# CarTalk.net
KiCad netlist of a schematic drawn in EAGLE
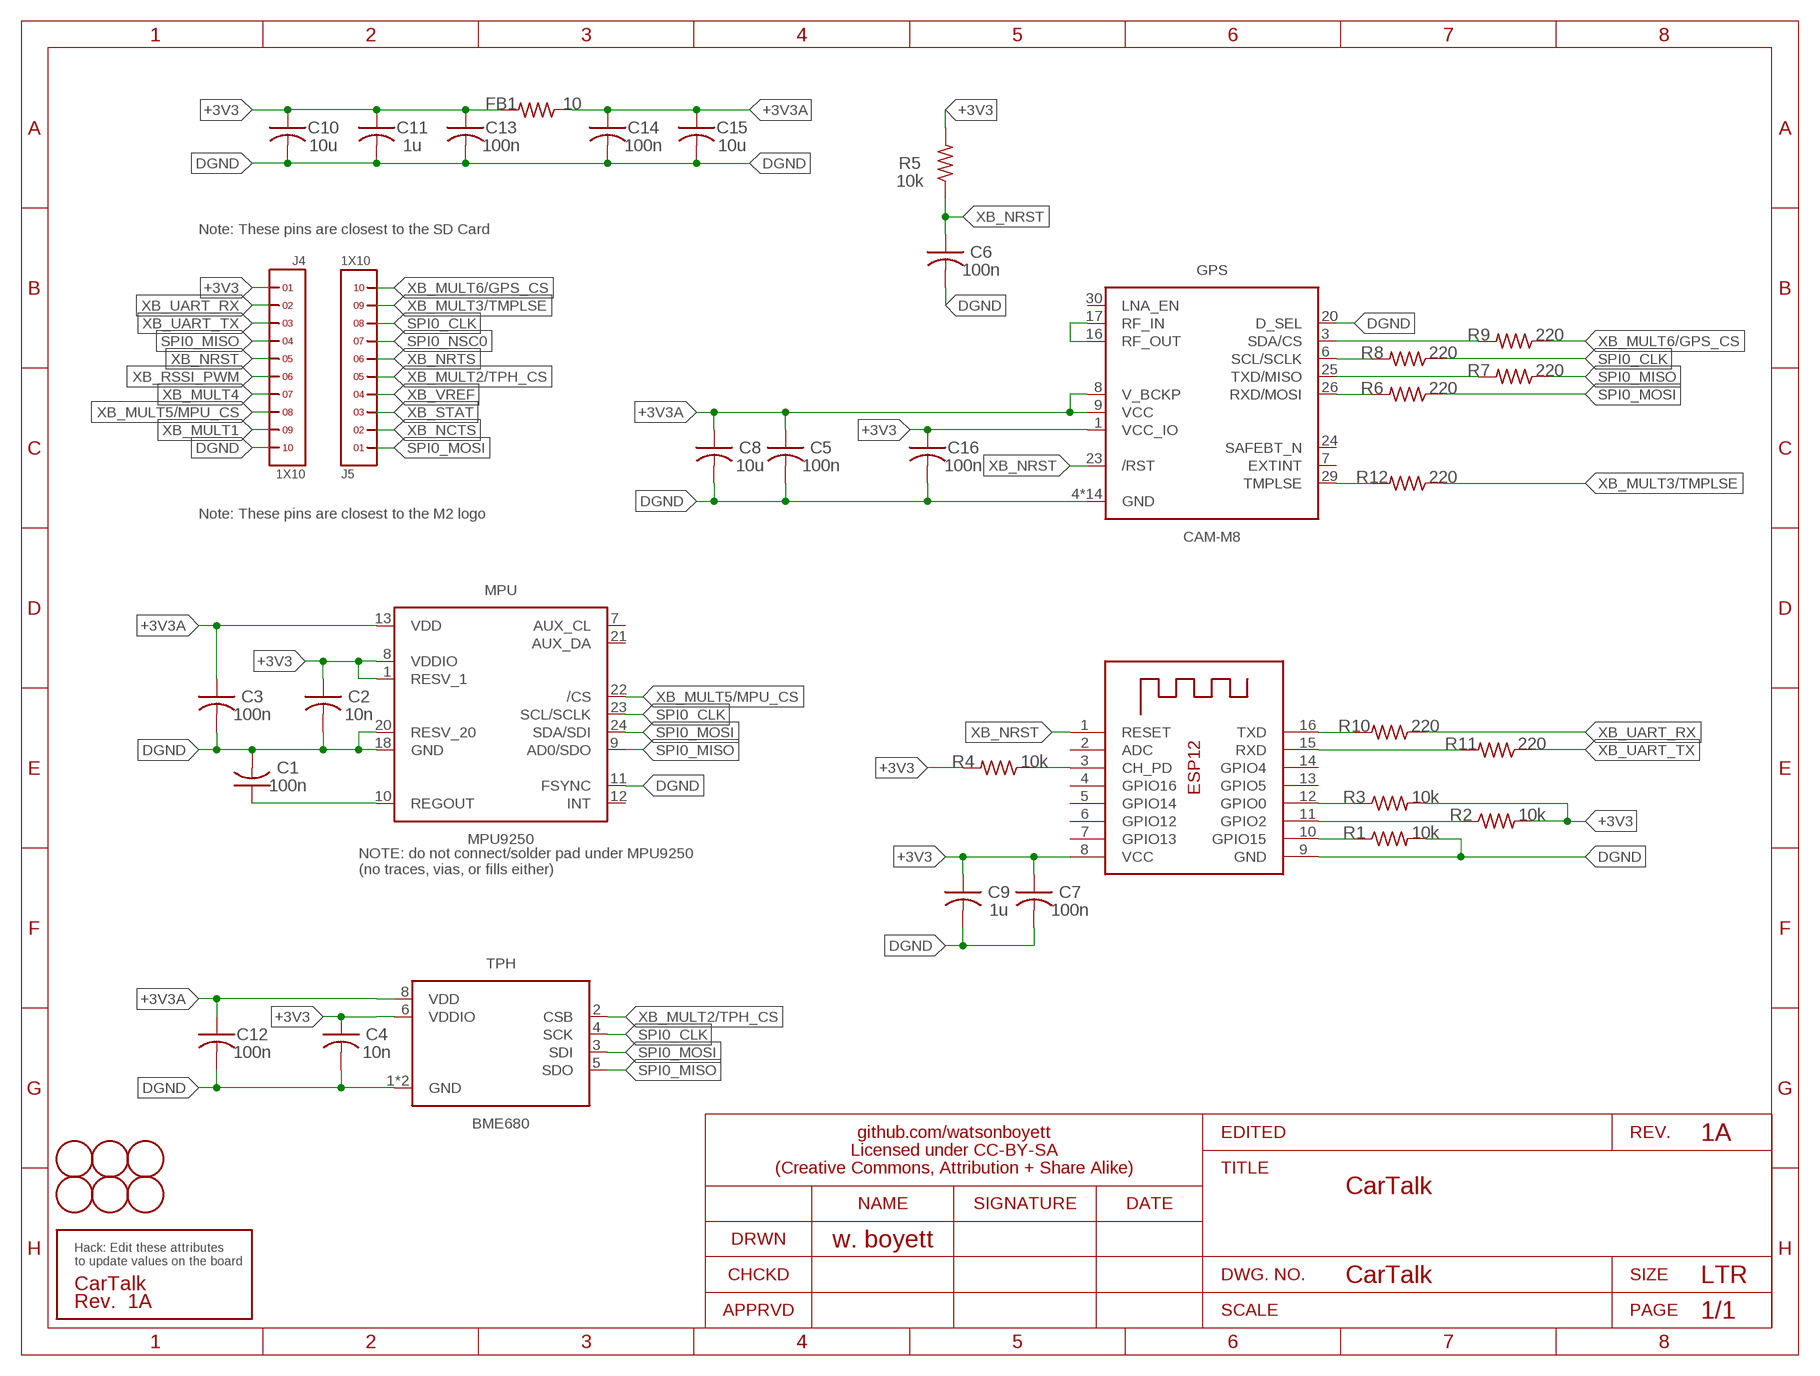
[diagram p0: schematic, sheet 1]

(export (version "E")
  (design (tool "Eeschema 10.0.6"))
  (components
    (comp (ref "C1")
      (value "100n")
      (footprint "eagle-import:C0603")
      (libsource (lib "eagle-import") (part "C-USC0603"))
    )
    (comp (ref "C2")
      (value "10n")
      (footprint "eagle-import:C0603")
      (libsource (lib "eagle-import") (part "C-USC0603"))
    )
    (comp (ref "C3")
      (value "100n")
      (footprint "eagle-import:C0603")
      (libsource (lib "eagle-import") (part "C-USC0603"))
    )
    (comp (ref "C4")
      (value "10n")
      (footprint "eagle-import:C0603")
      (libsource (lib "eagle-import") (part "C-USC0603"))
    )
    (comp (ref "C5")
      (value "100n")
      (footprint "eagle-import:C0603")
      (libsource (lib "eagle-import") (part "C-USC0603"))
    )
    (comp (ref "C6")
      (value "100n")
      (footprint "eagle-import:C0603")
      (libsource (lib "eagle-import") (part "C-USC0603"))
    )
    (comp (ref "C7")
      (value "100n")
      (footprint "eagle-import:C0603")
      (libsource (lib "eagle-import") (part "C-USC0603"))
    )
    (comp (ref "C8")
      (value "10u")
      (footprint "eagle-import:C0805")
      (libsource (lib "eagle-import") (part "C-USC0805"))
    )
    (comp (ref "C9")
      (value "1u")
      (footprint "eagle-import:C0603")
      (libsource (lib "eagle-import") (part "C-USC0603"))
    )
    (comp (ref "C10")
      (value "10u")
      (footprint "eagle-import:C0805")
      (libsource (lib "eagle-import") (part "C-USC0805"))
    )
    (comp (ref "C11")
      (value "1u")
      (footprint "eagle-import:C0603")
      (libsource (lib "eagle-import") (part "C-USC0603"))
    )
    (comp (ref "C12")
      (value "100n")
      (footprint "eagle-import:C0603")
      (libsource (lib "eagle-import") (part "C-USC0603"))
    )
    (comp (ref "C13")
      (value "100n")
      (footprint "eagle-import:C0603")
      (libsource (lib "eagle-import") (part "C-USC0603"))
    )
    (comp (ref "C14")
      (value "100n")
      (footprint "eagle-import:C0603")
      (libsource (lib "eagle-import") (part "C-USC0603"))
    )
    (comp (ref "C15")
      (value "10u")
      (footprint "eagle-import:C0805")
      (libsource (lib "eagle-import") (part "C-USC0805"))
    )
    (comp (ref "C16")
      (value "100n")
      (footprint "eagle-import:C0603")
      (libsource (lib "eagle-import") (part "C-USC0603"))
    )
    (comp (ref "FB1")
      (value "10")
      (footprint "eagle-import:R0603")
      (libsource (lib "eagle-import") (part "R-US_R0603"))
    )
    (comp (ref "GPS")
      (value "CAM-M8")
      (footprint "eagle-import:CAM-M8")
      (fields (field (name "MFG") "U-Blox America Inc.") (field (name "MPN") "CAM-M8Q-0"))
      (libsource (lib "eagle-import") (part "CAM-M8"))
    )
    (comp (ref "J4")
      (value "1X10")
      (footprint "eagle-import:1X10")
      (libsource (lib "eagle-import") (part "1X10"))
    )
    (comp (ref "J5")
      (value "1X10")
      (footprint "eagle-import:1X10")
      (libsource (lib "eagle-import") (part "1X10"))
    )
    (comp (ref "MPU")
      (value "MPU9250")
      (footprint "eagle-import:QFN24-NP")
      (fields (field (name "MFG") "TDK InvenSense") (field (name "MPN") "MPU-9250"))
      (libsource (lib "eagle-import") (part "MPU9250"))
    )
    (comp (ref "R1")
      (value "10k")
      (footprint "eagle-import:R0603")
      (libsource (lib "eagle-import") (part "R-US_R0603"))
    )
    (comp (ref "R2")
      (value "10k")
      (footprint "eagle-import:R0603")
      (libsource (lib "eagle-import") (part "R-US_R0603"))
    )
    (comp (ref "R3")
      (value "10k")
      (footprint "eagle-import:R0603")
      (libsource (lib "eagle-import") (part "R-US_R0603"))
    )
    (comp (ref "R4")
      (value "10k")
      (footprint "eagle-import:R0603")
      (libsource (lib "eagle-import") (part "R-US_R0603"))
    )
    (comp (ref "R5")
      (value "10k")
      (footprint "eagle-import:R0603")
      (libsource (lib "eagle-import") (part "R-US_R0603"))
    )
    (comp (ref "R6")
      (value "220")
      (footprint "eagle-import:R0603")
      (libsource (lib "eagle-import") (part "R-US_R0603"))
    )
    (comp (ref "R7")
      (value "220")
      (footprint "eagle-import:R0603")
      (libsource (lib "eagle-import") (part "R-US_R0603"))
    )
    (comp (ref "R8")
      (value "220")
      (footprint "eagle-import:R0603")
      (libsource (lib "eagle-import") (part "R-US_R0603"))
    )
    (comp (ref "R9")
      (value "220")
      (footprint "eagle-import:R0603")
      (libsource (lib "eagle-import") (part "R-US_R0603"))
    )
    (comp (ref "R10")
      (value "220")
      (footprint "eagle-import:R0603")
      (libsource (lib "eagle-import") (part "R-US_R0603"))
    )
    (comp (ref "R11")
      (value "220")
      (footprint "eagle-import:R0603")
      (libsource (lib "eagle-import") (part "R-US_R0603"))
    )
    (comp (ref "R12")
      (value "220")
      (footprint "eagle-import:R0603")
      (libsource (lib "eagle-import") (part "R-US_R0603"))
    )
    (comp (ref "TPH")
      (value "BME680")
      (footprint "eagle-import:BME-DFN8")
      (fields (field (name "MFG") "Bosch Sensortec"))
      (libsource (lib "eagle-import") (part "BME680"))
    )
    (comp (ref "U$5")
      (value "SILK_QC")
      (footprint "eagle-import:SILK_QC")
      (fields (field (name "MPN") "DNP") (field (name "PRODUCT") "CarTalk") (field (name "REV") "1A"))
      (libsource (lib "eagle-import") (part "SILK_QC"))
    )
    (comp (ref "U$6")
      (value "FIDUCIAL")
      (footprint "eagle-import:FIDUCIAL_1MM")
      (fields (field (name "MPN") "DNP"))
      (libsource (lib "eagle-import") (part "FIDUCIAL"))
    )
    (comp (ref "U$7")
      (value "FIDUCIAL")
      (footprint "eagle-import:FIDUCIAL_1MM")
      (fields (field (name "MPN") "DNP"))
      (libsource (lib "eagle-import") (part "FIDUCIAL"))
    )
    (comp (ref "U$8")
      (value "FIDUCIAL")
      (footprint "eagle-import:FIDUCIAL_1MM")
      (fields (field (name "MPN") "DNP"))
      (libsource (lib "eagle-import") (part "FIDUCIAL"))
    )
    (comp (ref "U$9")
      (value "FIDUCIAL")
      (footprint "eagle-import:FIDUCIAL_1MM")
      (fields (field (name "MPN") "DNP"))
      (libsource (lib "eagle-import") (part "FIDUCIAL"))
    )
    (comp (ref "U$10")
      (value "FIDUCIAL")
      (footprint "eagle-import:FIDUCIAL_1MM")
      (fields (field (name "MPN") "DNP"))
      (libsource (lib "eagle-import") (part "FIDUCIAL"))
    )
    (comp (ref "U$11")
      (value "FIDUCIAL")
      (footprint "eagle-import:FIDUCIAL_1MM")
      (fields (field (name "MPN") "DNP"))
      (libsource (lib "eagle-import") (part "FIDUCIAL"))
    )
    (comp (ref "WIFI")
      (value "ESP-12")
      (footprint "eagle-import:ESP-12")
      (libsource (lib "eagle-import") (part "ESP-12"))
    )
  )
  (nets
    (net (code "1") (name "+3V3") (class "Default")
      (node (ref "C10") (pin "1") (pinfunction "1_1") (pintype "passive"))
      (node (ref "C11") (pin "1") (pinfunction "1_1") (pintype "passive"))
      (node (ref "C13") (pin "1") (pinfunction "1_1") (pintype "passive"))
      (node (ref "C16") (pin "1") (pinfunction "1_1") (pintype "passive"))
      (node (ref "C2") (pin "1") (pinfunction "1_1") (pintype "passive"))
      (node (ref "C4") (pin "1") (pinfunction "1_1") (pintype "passive"))
      (node (ref "C7") (pin "1") (pinfunction "1_1") (pintype "passive"))
      (node (ref "C9") (pin "1") (pinfunction "1_1") (pintype "passive"))
      (node (ref "FB1") (pin "2") (pinfunction "2_2") (pintype "passive"))
      (node (ref "GPS") (pin "1") (pinfunction "VCC_IO_1") (pintype "bidirectional"))
      (node (ref "J4") (pin "1") (pinfunction "1_1") (pintype "bidirectional"))
      (node (ref "MPU") (pin "1") (pinfunction "RESV_1_1") (pintype "bidirectional"))
      (node (ref "MPU") (pin "8") (pinfunction "VDDIO_8") (pintype "bidirectional"))
      (node (ref "R1") (pin "2") (pinfunction "2_2") (pintype "passive"))
      (node (ref "R2") (pin "2") (pinfunction "2_2") (pintype "passive"))
      (node (ref "R4") (pin "2") (pinfunction "2_2") (pintype "passive"))
      (node (ref "R5") (pin "2") (pinfunction "2_2") (pintype "passive"))
      (node (ref "TPH") (pin "6") (pinfunction "VDDIO_6") (pintype "bidirectional"))
      (node (ref "WIFI") (pin "8") (pinfunction "VCC_8") (pintype "power_in"))
    )
    (net (code "2") (name "+3V3A") (class "Default")
      (node (ref "C12") (pin "1") (pinfunction "1_1") (pintype "passive"))
      (node (ref "C14") (pin "1") (pinfunction "1_1") (pintype "passive"))
      (node (ref "C15") (pin "1") (pinfunction "1_1") (pintype "passive"))
      (node (ref "C3") (pin "1") (pinfunction "1_1") (pintype "passive"))
      (node (ref "C5") (pin "1") (pinfunction "1_1") (pintype "passive"))
      (node (ref "C8") (pin "1") (pinfunction "1_1") (pintype "passive"))
      (node (ref "FB1") (pin "1") (pinfunction "1_1") (pintype "passive"))
      (node (ref "GPS") (pin "8") (pinfunction "V_BCKP_8") (pintype "bidirectional"))
      (node (ref "GPS") (pin "9") (pinfunction "VCC_9") (pintype "bidirectional"))
      (node (ref "MPU") (pin "13") (pinfunction "VDD_13") (pintype "bidirectional"))
      (node (ref "TPH") (pin "8") (pinfunction "VDD_8") (pintype "bidirectional"))
    )
    (net (code "3") (name "DGND") (class "Default")
      (node (ref "C1") (pin "2") (pinfunction "2_2") (pintype "passive"))
      (node (ref "C10") (pin "2") (pinfunction "2_2") (pintype "passive"))
      (node (ref "C11") (pin "2") (pinfunction "2_2") (pintype "passive"))
      (node (ref "C12") (pin "2") (pinfunction "2_2") (pintype "passive"))
      (node (ref "C13") (pin "2") (pinfunction "2_2") (pintype "passive"))
      (node (ref "C14") (pin "2") (pinfunction "2_2") (pintype "passive"))
      (node (ref "C15") (pin "2") (pinfunction "2_2") (pintype "passive"))
      (node (ref "C16") (pin "2") (pinfunction "2_2") (pintype "passive"))
      (node (ref "C2") (pin "2") (pinfunction "2_2") (pintype "passive"))
      (node (ref "C3") (pin "2") (pinfunction "2_2") (pintype "passive"))
      (node (ref "C4") (pin "2") (pinfunction "2_2") (pintype "passive"))
      (node (ref "C5") (pin "2") (pinfunction "2_2") (pintype "passive"))
      (node (ref "C6") (pin "2") (pinfunction "2_2") (pintype "passive"))
      (node (ref "C7") (pin "2") (pinfunction "2_2") (pintype "passive"))
      (node (ref "C8") (pin "2") (pinfunction "2_2") (pintype "passive"))
      (node (ref "C9") (pin "2") (pinfunction "2_2") (pintype "passive"))
      (node (ref "GPS") (pin "10") (pinfunction "GND_10") (pintype "bidirectional"))
      (node (ref "GPS") (pin "11") (pinfunction "GND_11") (pintype "bidirectional"))
      (node (ref "GPS") (pin "12") (pinfunction "GND_12") (pintype "bidirectional"))
      (node (ref "GPS") (pin "13") (pinfunction "GND_13") (pintype "bidirectional"))
      (node (ref "GPS") (pin "14") (pinfunction "GND_14") (pintype "bidirectional"))
      (node (ref "GPS") (pin "15") (pinfunction "GND_15") (pintype "bidirectional"))
      (node (ref "GPS") (pin "18") (pinfunction "GND_18") (pintype "bidirectional"))
      (node (ref "GPS") (pin "19") (pinfunction "GND_19") (pintype "bidirectional"))
      (node (ref "GPS") (pin "20") (pinfunction "D_SEL_20") (pintype "bidirectional"))
      (node (ref "GPS") (pin "21") (pinfunction "GND_21") (pintype "bidirectional"))
      (node (ref "GPS") (pin "22") (pinfunction "GND_22") (pintype "bidirectional"))
      (node (ref "GPS") (pin "27") (pinfunction "GND_27") (pintype "bidirectional"))
      (node (ref "GPS") (pin "31") (pinfunction "GND_31") (pintype "bidirectional"))
      (node (ref "GPS") (pin "4") (pinfunction "GND_4") (pintype "bidirectional"))
      (node (ref "GPS") (pin "5") (pinfunction "GND_5") (pintype "bidirectional"))
      (node (ref "J4") (pin "10") (pinfunction "10_10") (pintype "bidirectional"))
      (node (ref "MPU") (pin "11") (pinfunction "FSYNC_11") (pintype "bidirectional"))
      (node (ref "MPU") (pin "18") (pinfunction "GND_18") (pintype "bidirectional"))
      (node (ref "MPU") (pin "20") (pinfunction "RESV_20_20") (pintype "bidirectional"))
      (node (ref "R3") (pin "2") (pinfunction "2_2") (pintype "passive"))
      (node (ref "TPH") (pin "1") (pinfunction "GND_1") (pintype "bidirectional"))
      (node (ref "TPH") (pin "7") (pinfunction "GND_7") (pintype "bidirectional"))
      (node (ref "WIFI") (pin "9") (pinfunction "GND_9") (pintype "power_in"))
    )
    (net (code "4") (name "Net-(GPS-RF_IN)") (class "Default")
      (node (ref "GPS") (pin "16") (pinfunction "RF_OUT_16") (pintype "bidirectional"))
      (node (ref "GPS") (pin "17") (pinfunction "RF_IN_17") (pintype "bidirectional"))
    )
    (net (code "5") (name "Net-(GPS-RXD{slash}MOSI)") (class "Default")
      (node (ref "GPS") (pin "26") (pinfunction "RXD/MOSI_26") (pintype "bidirectional"))
      (node (ref "R6") (pin "2") (pinfunction "2_2") (pintype "passive"))
    )
    (net (code "6") (name "Net-(GPS-SCL{slash}SCLK)") (class "Default")
      (node (ref "GPS") (pin "6") (pinfunction "SCL/SCLK_6") (pintype "bidirectional"))
      (node (ref "R8") (pin "2") (pinfunction "2_2") (pintype "passive"))
    )
    (net (code "7") (name "Net-(GPS-SDA{slash}CS)") (class "Default")
      (node (ref "GPS") (pin "3") (pinfunction "SDA/CS_3") (pintype "bidirectional"))
      (node (ref "R9") (pin "2") (pinfunction "2_2") (pintype "passive"))
    )
    (net (code "8") (name "Net-(GPS-TMPLSE)") (class "Default")
      (node (ref "GPS") (pin "29") (pinfunction "TMPLSE_29") (pintype "bidirectional"))
      (node (ref "R12") (pin "2") (pinfunction "2_2") (pintype "passive"))
    )
    (net (code "9") (name "Net-(GPS-TXD{slash}MISO)") (class "Default")
      (node (ref "GPS") (pin "25") (pinfunction "TXD/MISO_25") (pintype "bidirectional"))
      (node (ref "R7") (pin "2") (pinfunction "2_2") (pintype "passive"))
    )
    (net (code "10") (name "Net-(MPU-REGOUT)") (class "Default")
      (node (ref "C1") (pin "1") (pinfunction "1_1") (pintype "passive"))
      (node (ref "MPU") (pin "10") (pinfunction "REGOUT_10") (pintype "bidirectional"))
    )
    (net (code "11") (name "Net-(WIFI-CH_PD)") (class "Default")
      (node (ref "R4") (pin "1") (pinfunction "1_1") (pintype "passive"))
      (node (ref "WIFI") (pin "3") (pinfunction "CH_PD_3") (pintype "input"))
    )
    (net (code "12") (name "Net-(WIFI-GPIO0)") (class "Default")
      (node (ref "R1") (pin "1") (pinfunction "1_1") (pintype "passive"))
      (node (ref "WIFI") (pin "12") (pinfunction "GPIO0_12") (pintype "bidirectional"))
    )
    (net (code "13") (name "Net-(WIFI-GPIO2)") (class "Default")
      (node (ref "R2") (pin "1") (pinfunction "1_1") (pintype "passive"))
      (node (ref "WIFI") (pin "11") (pinfunction "GPIO2_11") (pintype "bidirectional"))
    )
    (net (code "14") (name "Net-(WIFI-GPIO15)") (class "Default")
      (node (ref "R3") (pin "1") (pinfunction "1_1") (pintype "passive"))
      (node (ref "WIFI") (pin "10") (pinfunction "GPIO15_10") (pintype "bidirectional"))
    )
    (net (code "15") (name "Net-(WIFI-RXD)") (class "Default")
      (node (ref "R11") (pin "2") (pinfunction "2_2") (pintype "passive"))
      (node (ref "WIFI") (pin "15") (pinfunction "RXD_15") (pintype "input"))
    )
    (net (code "16") (name "Net-(WIFI-TXD)") (class "Default")
      (node (ref "R10") (pin "2") (pinfunction "2_2") (pintype "passive"))
      (node (ref "WIFI") (pin "16") (pinfunction "TXD_16") (pintype "output"))
    )
    (net (code "17") (name "SPI0_CLK") (class "Default")
      (node (ref "J5") (pin "8") (pinfunction "8_8") (pintype "bidirectional"))
      (node (ref "MPU") (pin "23") (pinfunction "SCL/SCLK_23") (pintype "bidirectional"))
      (node (ref "R8") (pin "1") (pinfunction "1_1") (pintype "passive"))
      (node (ref "TPH") (pin "4") (pinfunction "SCK_4") (pintype "bidirectional"))
    )
    (net (code "18") (name "SPI0_MISO") (class "Default")
      (node (ref "J4") (pin "4") (pinfunction "4_4") (pintype "bidirectional"))
      (node (ref "MPU") (pin "9") (pinfunction "AD0/SDO_9") (pintype "bidirectional"))
      (node (ref "R7") (pin "1") (pinfunction "1_1") (pintype "passive"))
      (node (ref "TPH") (pin "5") (pinfunction "SDO_5") (pintype "bidirectional"))
    )
    (net (code "19") (name "SPI0_MOSI") (class "Default")
      (node (ref "J5") (pin "1") (pinfunction "1_1") (pintype "bidirectional"))
      (node (ref "MPU") (pin "24") (pinfunction "SDA/SDI_24") (pintype "bidirectional"))
      (node (ref "R6") (pin "1") (pinfunction "1_1") (pintype "passive"))
      (node (ref "TPH") (pin "3") (pinfunction "SDI_3") (pintype "bidirectional"))
    )
    (net (code "20") (name "SPI0_NSC0") (class "Default")
      (node (ref "J5") (pin "7") (pinfunction "7_7") (pintype "bidirectional"))
    )
    (net (code "21") (name "XB_MULT1") (class "Default")
      (node (ref "J4") (pin "9") (pinfunction "9_9") (pintype "bidirectional"))
    )
    (net (code "22") (name "XB_MULT2{slash}TPH_CS") (class "Default")
      (node (ref "J5") (pin "5") (pinfunction "5_5") (pintype "bidirectional"))
      (node (ref "TPH") (pin "2") (pinfunction "CSB_2") (pintype "bidirectional"))
    )
    (net (code "23") (name "XB_MULT3{slash}TMPLSE") (class "Default")
      (node (ref "J5") (pin "9") (pinfunction "9_9") (pintype "bidirectional"))
      (node (ref "R12") (pin "1") (pinfunction "1_1") (pintype "passive"))
    )
    (net (code "24") (name "XB_MULT4") (class "Default")
      (node (ref "J4") (pin "7") (pinfunction "7_7") (pintype "bidirectional"))
    )
    (net (code "25") (name "XB_MULT5{slash}MPU_CS") (class "Default")
      (node (ref "J4") (pin "8") (pinfunction "8_8") (pintype "bidirectional"))
      (node (ref "MPU") (pin "22") (pinfunction "/CS_22") (pintype "bidirectional"))
    )
    (net (code "26") (name "XB_MULT6{slash}GPS_CS") (class "Default")
      (node (ref "J5") (pin "10") (pinfunction "10_10") (pintype "bidirectional"))
      (node (ref "R9") (pin "1") (pinfunction "1_1") (pintype "passive"))
    )
    (net (code "27") (name "XB_NCTS") (class "Default")
      (node (ref "J5") (pin "2") (pinfunction "2_2") (pintype "bidirectional"))
    )
    (net (code "28") (name "XB_NRST") (class "Default")
      (node (ref "C6") (pin "1") (pinfunction "1_1") (pintype "passive"))
      (node (ref "GPS") (pin "23") (pinfunction "/RST_23") (pintype "bidirectional"))
      (node (ref "J4") (pin "5") (pinfunction "5_5") (pintype "bidirectional"))
      (node (ref "R5") (pin "1") (pinfunction "1_1") (pintype "passive"))
      (node (ref "WIFI") (pin "1") (pinfunction "RESET_1") (pintype "input"))
    )
    (net (code "29") (name "XB_NRTS") (class "Default")
      (node (ref "J5") (pin "6") (pinfunction "6_6") (pintype "bidirectional"))
    )
    (net (code "30") (name "XB_RSSI_PWM") (class "Default")
      (node (ref "J4") (pin "6") (pinfunction "6_6") (pintype "bidirectional"))
    )
    (net (code "31") (name "XB_STAT") (class "Default")
      (node (ref "J5") (pin "3") (pinfunction "3_3") (pintype "bidirectional"))
    )
    (net (code "32") (name "XB_UART_RX") (class "Default")
      (node (ref "J4") (pin "2") (pinfunction "2_2") (pintype "bidirectional"))
      (node (ref "R10") (pin "1") (pinfunction "1_1") (pintype "passive"))
    )
    (net (code "33") (name "XB_UART_TX") (class "Default")
      (node (ref "J4") (pin "3") (pinfunction "3_3") (pintype "bidirectional"))
      (node (ref "R11") (pin "1") (pinfunction "1_1") (pintype "passive"))
    )
    (net (code "34") (name "XB_VREF") (class "Default")
      (node (ref "J5") (pin "4") (pinfunction "4_4") (pintype "bidirectional"))
    )
    (net (code "35") (name "unconnected-(GPS-EXTINT-Pad7)") (class "Default")
      (node (ref "GPS") (pin "7") (pinfunction "EXTINT_7") (pintype "bidirectional"))
    )
    (net (code "36") (name "unconnected-(GPS-LNA_EN-Pad30)") (class "Default")
      (node (ref "GPS") (pin "30") (pinfunction "LNA_EN_30") (pintype "bidirectional"))
    )
    (net (code "37") (name "unconnected-(GPS-SAFEBT_N-Pad24)") (class "Default")
      (node (ref "GPS") (pin "24") (pinfunction "SAFEBT_N_24") (pintype "bidirectional"))
    )
    (net (code "38") (name "unconnected-(MPU-AUX_CL-Pad7)") (class "Default")
      (node (ref "MPU") (pin "7") (pinfunction "AUX_CL_7") (pintype "bidirectional"))
    )
    (net (code "39") (name "unconnected-(MPU-AUX_DA-Pad21)") (class "Default")
      (node (ref "MPU") (pin "21") (pinfunction "AUX_DA_21") (pintype "bidirectional"))
    )
    (net (code "40") (name "unconnected-(MPU-INT-Pad12)") (class "Default")
      (node (ref "MPU") (pin "12") (pinfunction "INT_12") (pintype "bidirectional"))
    )
    (net (code "41") (name "unconnected-(WIFI-ADC-Pad2)") (class "Default")
      (node (ref "WIFI") (pin "2") (pinfunction "ADC_2") (pintype "passive"))
    )
    (net (code "42") (name "unconnected-(WIFI-GPIO4-Pad14)") (class "Default")
      (node (ref "WIFI") (pin "14") (pinfunction "GPIO4_14") (pintype "bidirectional"))
    )
    (net (code "43") (name "unconnected-(WIFI-GPIO5-Pad13)") (class "Default")
      (node (ref "WIFI") (pin "13") (pinfunction "GPIO5_13") (pintype "bidirectional"))
    )
    (net (code "44") (name "unconnected-(WIFI-GPIO12-Pad6)") (class "Default")
      (node (ref "WIFI") (pin "6") (pinfunction "GPIO12_6") (pintype "bidirectional"))
    )
    (net (code "45") (name "unconnected-(WIFI-GPIO13-Pad7)") (class "Default")
      (node (ref "WIFI") (pin "7") (pinfunction "GPIO13_7") (pintype "bidirectional"))
    )
    (net (code "46") (name "unconnected-(WIFI-GPIO14-Pad5)") (class "Default")
      (node (ref "WIFI") (pin "5") (pinfunction "GPIO14_5") (pintype "bidirectional"))
    )
    (net (code "47") (name "unconnected-(WIFI-GPIO16-Pad4)") (class "Default")
      (node (ref "WIFI") (pin "4") (pinfunction "GPIO16_4") (pintype "bidirectional"))
    )
  )
)
